# BGA_LEDs_C.net
KiCad netlist of a schematic drawn in Altium Designer
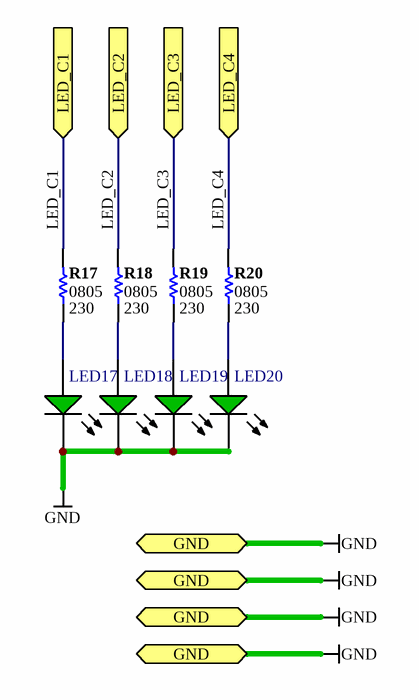
[diagram p0: BGA LEDs C.SchDoc]

(export (version "E")
  (design (tool "Eeschema 10.0.6"))
  (components
    (comp (ref "LED17")
      (value "LED_1206")
      (footprint "RESC0805(2012)70_L")
      (description "GREEN color, 1206, SMD")
      (libsource (lib "Component_DB") (part "LED_GREEN_A1K2-2.A1"))
    )
    (comp (ref "LED18")
      (value "LED_1206")
      (footprint "RESC0805(2012)70_L")
      (description "GREEN color, 1206, SMD")
      (libsource (lib "Component_DB") (part "LED_GREEN_A1K2-2.A1"))
    )
    (comp (ref "LED19")
      (value "LED_1206")
      (footprint "RESC0805(2012)70_L")
      (description "GREEN color, 1206, SMD")
      (libsource (lib "Component_DB") (part "LED_GREEN_A1K2-2.A1"))
    )
    (comp (ref "LED20")
      (value "LED_1206")
      (footprint "RESC0805(2012)70_L")
      (description "GREEN color, 1206, SMD")
      (libsource (lib "Component_DB") (part "LED_GREEN_A1K2-2.A1"))
    )
    (comp (ref "R17")
      (value "0805")
      (footprint "RESC0805(2012)70_L")
      (description "Jumper 0805 (2012 Metric)")
      (fields (field (name "VALUE (OHMS)") "230") (field (name "POWER") "None"))
      (libsource (lib "Component_DB") (part "RES"))
    )
    (comp (ref "R18")
      (value "0805")
      (footprint "RESC0805(2012)70_L")
      (description "Jumper 0805 (2012 Metric)")
      (fields (field (name "VALUE (OHMS)") "230") (field (name "POWER") "None"))
      (libsource (lib "Component_DB") (part "RES"))
    )
    (comp (ref "R19")
      (value "0805")
      (footprint "RESC0805(2012)70_L")
      (description "Jumper 0805 (2012 Metric)")
      (fields (field (name "VALUE (OHMS)") "230") (field (name "POWER") "None"))
      (libsource (lib "Component_DB") (part "RES"))
    )
    (comp (ref "R20")
      (value "0805")
      (footprint "RESC0805(2012)70_L")
      (description "Jumper 0805 (2012 Metric)")
      (fields (field (name "VALUE (OHMS)") "230") (field (name "POWER") "None"))
      (libsource (lib "Component_DB") (part "RES"))
    )
  )
  (nets
    (net (code "1") (name "/LED_C1") (class "Default")
      (node (ref "R17") (pin "2") (pinfunction "2_2") (pintype "passive"))
    )
    (net (code "2") (name "/LED_C2") (class "Default")
      (node (ref "R18") (pin "2") (pinfunction "2_2") (pintype "passive"))
    )
    (net (code "3") (name "/LED_C3") (class "Default")
      (node (ref "R19") (pin "2") (pinfunction "2_2") (pintype "passive"))
    )
    (net (code "4") (name "/LED_C4") (class "Default")
      (node (ref "R20") (pin "2") (pinfunction "2_2") (pintype "passive"))
    )
    (net (code "5") (name "GND") (class "Default")
      (node (ref "LED17") (pin "2") (pinfunction "K_2") (pintype "passive"))
      (node (ref "LED18") (pin "2") (pinfunction "K_2") (pintype "passive"))
      (node (ref "LED19") (pin "2") (pinfunction "K_2") (pintype "passive"))
      (node (ref "LED20") (pin "2") (pinfunction "K_2") (pintype "passive"))
    )
    (net (code "6") (name "Net-(LED17-A)") (class "Default")
      (node (ref "LED17") (pin "1") (pinfunction "A_1") (pintype "passive"))
      (node (ref "R17") (pin "1") (pinfunction "1_1") (pintype "passive"))
    )
    (net (code "7") (name "Net-(LED18-A)") (class "Default")
      (node (ref "LED18") (pin "1") (pinfunction "A_1") (pintype "passive"))
      (node (ref "R18") (pin "1") (pinfunction "1_1") (pintype "passive"))
    )
    (net (code "8") (name "Net-(LED19-A)") (class "Default")
      (node (ref "LED19") (pin "1") (pinfunction "A_1") (pintype "passive"))
      (node (ref "R19") (pin "1") (pinfunction "1_1") (pintype "passive"))
    )
    (net (code "9") (name "Net-(LED20-A)") (class "Default")
      (node (ref "LED20") (pin "1") (pinfunction "A_1") (pintype "passive"))
      (node (ref "R20") (pin "1") (pinfunction "1_1") (pintype "passive"))
    )
  )
)
